# lab1_yakimenko_usb_i2c.net
KiCad netlist of a schematic drawn in Altium Designer
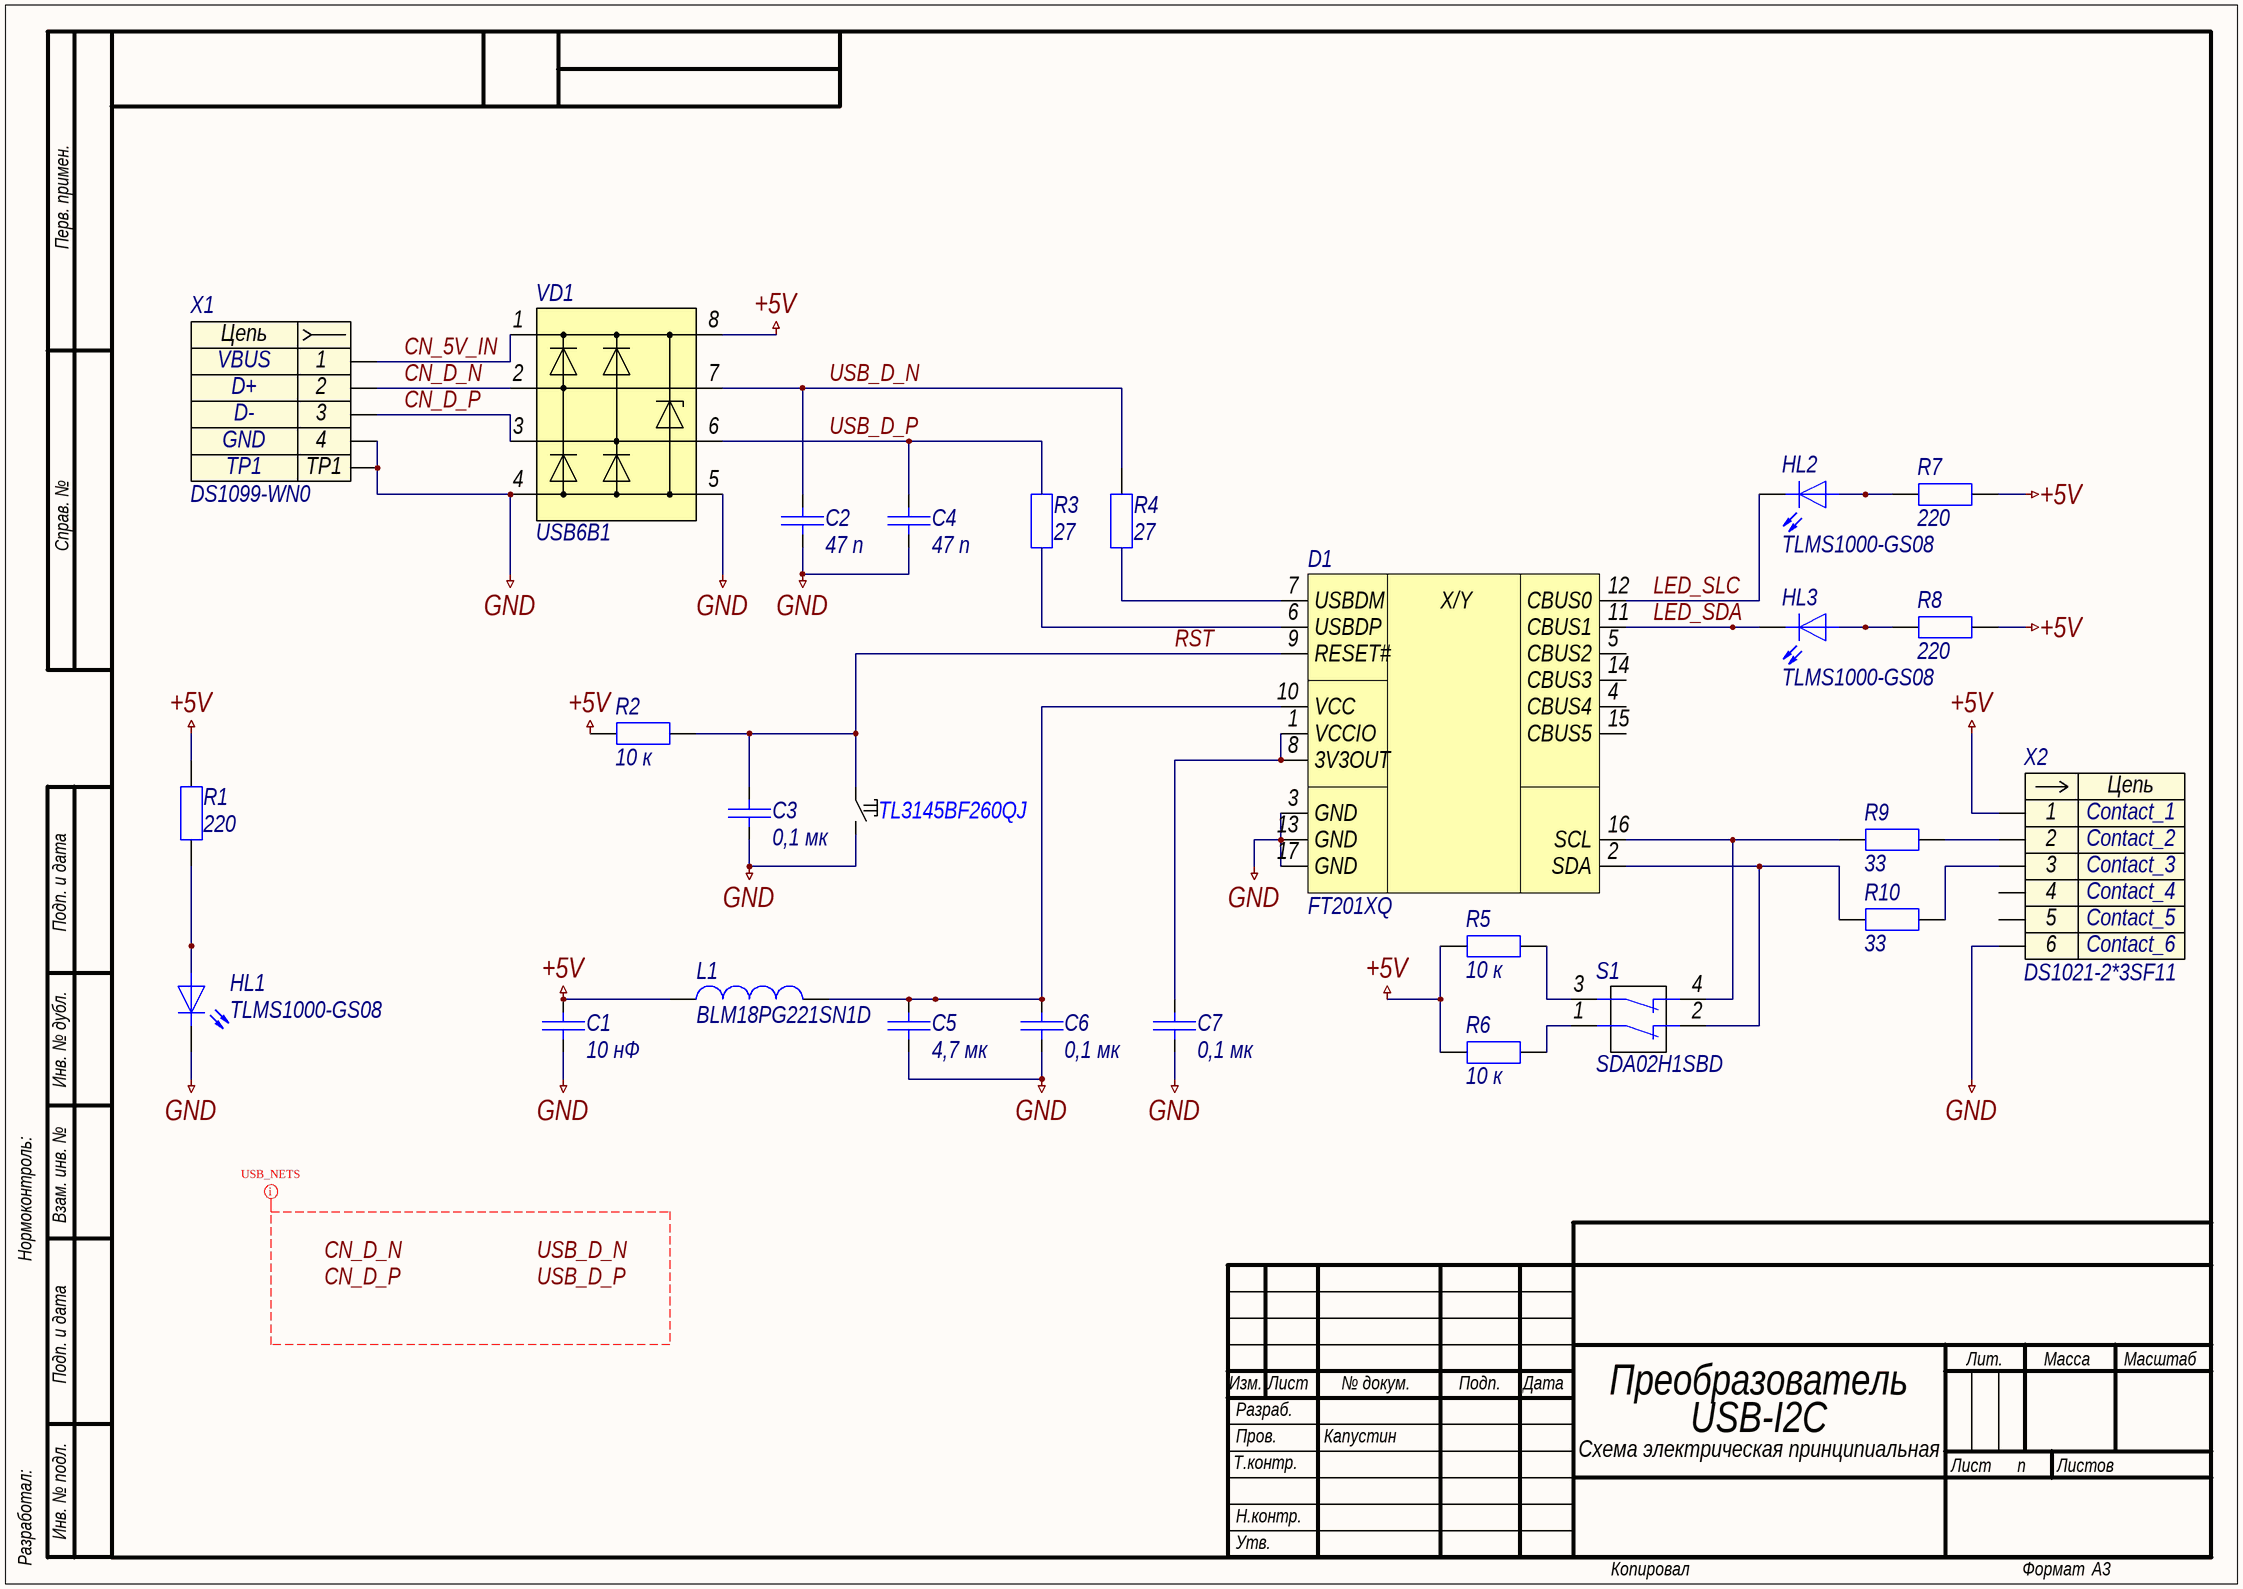
[diagram p0: lab1_yakimenko_usb_i2c.SchDoc]

(export (version "E")
  (design (tool "Eeschema 10.0.6"))
  (components
    (comp (ref "C1")
      (value "10 нФ")
      (footprint "C0402")
      (description "=Описание")
      (libsource (lib "Database_Students") (part "C-NONPOLAR"))
    )
    (comp (ref "C2")
      (value "47 п")
      (footprint "C0201")
      (description "=Описание")
      (libsource (lib "Database_Students") (part "C-NONPOLAR"))
    )
    (comp (ref "C3")
      (value "0,1 мк")
      (footprint "C0603")
      (description "=Описание")
      (libsource (lib "Database_Students") (part "C-NONPOLAR"))
    )
    (comp (ref "C4")
      (value "47 п")
      (footprint "C0201")
      (description "=Описание")
      (libsource (lib "Database_Students") (part "C-NONPOLAR"))
    )
    (comp (ref "C5")
      (value "4,7 мк")
      (footprint "C0603")
      (description "=Описание")
      (libsource (lib "Database_Students") (part "C-NONPOLAR"))
    )
    (comp (ref "C6")
      (value "0,1 мк")
      (footprint "C0603")
      (description "=Описание")
      (libsource (lib "Database_Students") (part "C-NONPOLAR"))
    )
    (comp (ref "C7")
      (value "0,1 мк")
      (footprint "C0603")
      (description "=Описание")
      (libsource (lib "Database_Students") (part "C-NONPOLAR"))
    )
    (comp (ref "D1") (value "FT201XQ") (footprint "FT201XQ") (libsource (lib "Schlib1") (part "FT201XQ")))
    (comp (ref "HL1")
      (value "TLMS1000-GS08")
      (footprint "HL0603")
      (description "=Описание")
      (libsource (lib "Database_Students") (part "HL-COMMON"))
    )
    (comp (ref "HL2")
      (value "TLMS1000-GS08")
      (footprint "HL0603")
      (description "=Описание")
      (libsource (lib "Database_Students") (part "HL-COMMON"))
    )
    (comp (ref "HL3")
      (value "TLMS1000-GS08")
      (footprint "HL0603")
      (description "=Описание")
      (libsource (lib "Database_Students") (part "HL-COMMON"))
    )
    (comp (ref "L1")
      (value "BLM18PG221SN1D")
      (footprint "BLM-2-0603")
      (description "=Описание")
      (libsource (lib "Database_Students") (part "FERRITE-BEAD"))
    )
    (comp (ref "R1")
      (value "220")
      (footprint "R0603")
      (description "=Описание")
      (libsource (lib "Database_Students") (part "R-COMMON"))
    )
    (comp (ref "R2")
      (value "10 к")
      (footprint "R0603")
      (description "=Описание")
      (libsource (lib "Database_Students") (part "R-COMMON"))
    )
    (comp (ref "R3") (value "27") (footprint "R27") (libsource (lib "Schlib2") (part "R27")))
    (comp (ref "R4") (value "27") (footprint "R27") (libsource (lib "Schlib2") (part "R27")))
    (comp (ref "R5")
      (value "10 к")
      (footprint "R0603")
      (description "=Описание")
      (libsource (lib "Database_Students") (part "R-COMMON"))
    )
    (comp (ref "R6")
      (value "10 к")
      (footprint "R0603")
      (description "=Описание")
      (libsource (lib "Database_Students") (part "R-COMMON"))
    )
    (comp (ref "R7")
      (value "220")
      (footprint "R0603")
      (description "=Описание")
      (libsource (lib "Database_Students") (part "R-COMMON"))
    )
    (comp (ref "R8")
      (value "220")
      (footprint "R0603")
      (description "=Описание")
      (libsource (lib "Database_Students") (part "R-COMMON"))
    )
    (comp (ref "R9")
      (value "33")
      (footprint "R0603")
      (description "=Описание")
      (libsource (lib "Database_Students") (part "R-COMMON"))
    )
    (comp (ref "R10")
      (value "33")
      (footprint "R0603")
      (description "=Описание")
      (libsource (lib "Database_Students") (part "R-COMMON"))
    )
    (comp (ref "S1")
      (value "SDA02H1SBD")
      (footprint "DIP-SWITCH-02-706X930X545")
      (description "=Описание")
      (libsource (lib "Database_Students") (part "SWITCH-02"))
    )
    (comp (ref "TL3145BF260QJ")
      (value "~")
      (footprint "BUT: 3x4x2 SMT")
      (description "SMT 3*4*2 2PIN")
      (fields
        (field (name "MANUFACTURER") "xin cheng electronic")
        (field (name "VALUEMANUFACTURERPARTNUMBER") ", 3*4*2mm")
      )
      (libsource (lib "electromechanics") (part "Button_3x4x2_SMT"))
    )
    (comp (ref "VD1")
      (value "USB6B1")
      (footprint "SO-8")
      (description "=Описание")
      (libsource (lib "Database_Students") (part "USB6B1"))
    )
    (comp (ref "X1")
      (value "DS1099-WN0")
      (footprint "DS1099-WN0")
      (description "=Описание")
      (libsource (lib "Database_Students") (part "HEADER-4-TP1-SCT"))
    )
    (comp (ref "X2")
      (value "DS1021-2*3SF11")
      (footprint "DS1021-2X3SF11")
      (description "=Описание")
      (libsource (lib "Database_Students") (part "HEADER-6-PLG"))
    )
  )
  (nets
    (net (code "1") (name "+5V") (class "Default")
      (node (ref "C1") (pin "1") (pinfunction "1_1") (pintype "passive"))
      (node (ref "L1") (pin "1") (pinfunction "1_1") (pintype "passive"))
      (node (ref "R1") (pin "2") (pinfunction "2_2") (pintype "passive"))
      (node (ref "R2") (pin "1") (pinfunction "1_1") (pintype "passive"))
      (node (ref "R5") (pin "1") (pinfunction "1_1") (pintype "passive"))
      (node (ref "R6") (pin "1") (pinfunction "1_1") (pintype "passive"))
      (node (ref "R7") (pin "2") (pinfunction "2_2") (pintype "passive"))
      (node (ref "R8") (pin "2") (pinfunction "2_2") (pintype "passive"))
      (node (ref "VD1") (pin "8") (pinfunction "8_8") (pintype "passive"))
      (node (ref "X2") (pin "1") (pinfunction "1_1") (pintype "passive"))
    )
    (net (code "2") (name "/CN_5V_IN") (class "Default")
      (node (ref "VD1") (pin "1") (pinfunction "1_1") (pintype "passive"))
      (node (ref "X1") (pin "1") (pinfunction "1_1") (pintype "passive"))
    )
    (net (code "3") (name "/CN_D_N") (class "Default")
      (node (ref "VD1") (pin "2") (pinfunction "2_2") (pintype "passive"))
      (node (ref "X1") (pin "2") (pinfunction "2_2") (pintype "passive"))
    )
    (net (code "4") (name "/CN_D_P") (class "Default")
      (node (ref "VD1") (pin "3") (pinfunction "3_3") (pintype "passive"))
      (node (ref "X1") (pin "3") (pinfunction "3_3") (pintype "passive"))
    )
    (net (code "5") (name "/LED_SDA") (class "Default")
      (node (ref "D1") (pin "11") (pinfunction "CBUS1_11") (pintype "passive"))
      (node (ref "HL3") (pin "1") (pinfunction "1_1") (pintype "passive"))
    )
    (net (code "6") (name "/LED_SLC") (class "Default")
      (node (ref "D1") (pin "12") (pinfunction "CBUS0_12") (pintype "passive"))
      (node (ref "HL2") (pin "1") (pinfunction "1_1") (pintype "passive"))
    )
    (net (code "7") (name "/RST") (class "Default")
      (node (ref "C3") (pin "1") (pinfunction "1_1") (pintype "passive"))
      (node (ref "D1") (pin "9") (pinfunction "RESET#_9") (pintype "passive"))
      (node (ref "R2") (pin "2") (pinfunction "2_2") (pintype "passive"))
      (node (ref "TL3145BF260QJ") (pin "1") (pinfunction "1_1") (pintype "passive"))
    )
    (net (code "8") (name "/USB_D_N") (class "Default")
      (node (ref "C2") (pin "1") (pinfunction "1_1") (pintype "passive"))
      (node (ref "VD1") (pin "7") (pinfunction "7_7") (pintype "passive"))
    )
    (net (code "9") (name "/USB_D_P") (class "Default")
      (node (ref "C4") (pin "1") (pinfunction "1_1") (pintype "passive"))
      (node (ref "R3") (pin "2") (pinfunction "2_2") (pintype "passive"))
      (node (ref "VD1") (pin "6") (pinfunction "6_6") (pintype "passive"))
    )
    (net (code "10") (name "GND") (class "Default")
      (node (ref "C1") (pin "2") (pinfunction "2_2") (pintype "passive"))
      (node (ref "C2") (pin "2") (pinfunction "2_2") (pintype "passive"))
      (node (ref "C3") (pin "2") (pinfunction "2_2") (pintype "passive"))
      (node (ref "C4") (pin "2") (pinfunction "2_2") (pintype "passive"))
      (node (ref "C5") (pin "2") (pinfunction "2_2") (pintype "passive"))
      (node (ref "C6") (pin "2") (pinfunction "2_2") (pintype "passive"))
      (node (ref "C7") (pin "2") (pinfunction "2_2") (pintype "passive"))
      (node (ref "D1") (pin "13") (pinfunction "GND_13") (pintype "passive"))
      (node (ref "D1") (pin "17") (pinfunction "GND_17") (pintype "passive"))
      (node (ref "D1") (pin "3") (pinfunction "GND_3") (pintype "passive"))
      (node (ref "HL1") (pin "1") (pinfunction "1_1") (pintype "passive"))
      (node (ref "TL3145BF260QJ") (pin "2") (pinfunction "2_2") (pintype "passive"))
      (node (ref "VD1") (pin "4") (pinfunction "4_4") (pintype "passive"))
      (node (ref "VD1") (pin "5") (pinfunction "5_5") (pintype "passive"))
      (node (ref "X1") (pin "4") (pinfunction "4_4") (pintype "passive"))
      (node (ref "X1") (pin "TP1") (pinfunction "TP1_TP1") (pintype "passive"))
      (node (ref "X2") (pin "6") (pinfunction "6_6") (pintype "passive"))
    )
    (net (code "11") (name "Net-(D1-3V3OUT)") (class "Default")
      (node (ref "C7") (pin "1") (pinfunction "1_1") (pintype "passive"))
      (node (ref "D1") (pin "1") (pinfunction "VCCIO_1") (pintype "passive"))
      (node (ref "D1") (pin "8") (pinfunction "3V3OUT_8") (pintype "passive"))
    )
    (net (code "12") (name "Net-(D1-SCL)") (class "Default")
      (node (ref "D1") (pin "16") (pinfunction "SCL_16") (pintype "passive"))
      (node (ref "R9") (pin "1") (pinfunction "1_1") (pintype "passive"))
      (node (ref "S1") (pin "4") (pinfunction "4_4") (pintype "passive"))
    )
    (net (code "13") (name "Net-(D1-SDA)") (class "Default")
      (node (ref "D1") (pin "2") (pinfunction "SDA_2") (pintype "passive"))
      (node (ref "R10") (pin "1") (pinfunction "1_1") (pintype "passive"))
      (node (ref "S1") (pin "2") (pinfunction "2_2") (pintype "passive"))
    )
    (net (code "14") (name "Net-(D1-USBDM)") (class "Default")
      (node (ref "D1") (pin "7") (pinfunction "USBDM_7") (pintype "passive"))
      (node (ref "R4") (pin "1") (pinfunction "1_1") (pintype "passive"))
    )
    (net (code "15") (name "Net-(D1-USBDP)") (class "Default")
      (node (ref "D1") (pin "6") (pinfunction "USBDP_6") (pintype "passive"))
      (node (ref "R3") (pin "1") (pinfunction "1_1") (pintype "passive"))
    )
    (net (code "16") (name "Net-(D1-VCC)") (class "Default")
      (node (ref "C5") (pin "1") (pinfunction "1_1") (pintype "passive"))
      (node (ref "C6") (pin "1") (pinfunction "1_1") (pintype "passive"))
      (node (ref "D1") (pin "10") (pinfunction "VCC_10") (pintype "passive"))
      (node (ref "L1") (pin "2") (pinfunction "2_2") (pintype "passive"))
    )
    (net (code "17") (name "Net-(HL1-Pad2)") (class "Default")
      (node (ref "HL1") (pin "2") (pinfunction "2_2") (pintype "passive"))
      (node (ref "R1") (pin "1") (pinfunction "1_1") (pintype "passive"))
    )
    (net (code "18") (name "Net-(HL2-Pad2)") (class "Default")
      (node (ref "HL2") (pin "2") (pinfunction "2_2") (pintype "passive"))
      (node (ref "R7") (pin "1") (pinfunction "1_1") (pintype "passive"))
    )
    (net (code "19") (name "Net-(HL3-Pad2)") (class "Default")
      (node (ref "HL3") (pin "2") (pinfunction "2_2") (pintype "passive"))
      (node (ref "R8") (pin "1") (pinfunction "1_1") (pintype "passive"))
    )
    (net (code "20") (name "Net-(R5-Pad2)") (class "Default")
      (node (ref "R5") (pin "2") (pinfunction "2_2") (pintype "passive"))
      (node (ref "S1") (pin "3") (pinfunction "3_3") (pintype "passive"))
    )
    (net (code "21") (name "Net-(R6-Pad2)") (class "Default")
      (node (ref "R6") (pin "2") (pinfunction "2_2") (pintype "passive"))
      (node (ref "S1") (pin "1") (pinfunction "1_1") (pintype "passive"))
    )
    (net (code "22") (name "Net-(R9-Pad2)") (class "Default")
      (node (ref "R9") (pin "2") (pinfunction "2_2") (pintype "passive"))
      (node (ref "X2") (pin "2") (pinfunction "2_2") (pintype "passive"))
    )
    (net (code "23") (name "Net-(R10-Pad2)") (class "Default")
      (node (ref "R10") (pin "2") (pinfunction "2_2") (pintype "passive"))
      (node (ref "X2") (pin "3") (pinfunction "3_3") (pintype "passive"))
    )
    (net (code "24") (name "unconnected-(D1-CBUS2-Pad5)") (class "Default")
      (node (ref "D1") (pin "5") (pinfunction "CBUS2_5") (pintype "passive"))
    )
    (net (code "25") (name "unconnected-(D1-CBUS3-Pad14)") (class "Default")
      (node (ref "D1") (pin "14") (pinfunction "CBUS3_14") (pintype "passive"))
    )
    (net (code "26") (name "unconnected-(D1-CBUS4-Pad4)") (class "Default")
      (node (ref "D1") (pin "4") (pinfunction "CBUS4_4") (pintype "passive"))
    )
    (net (code "27") (name "unconnected-(D1-CBUS5-Pad15)") (class "Default")
      (node (ref "D1") (pin "15") (pinfunction "CBUS5_15") (pintype "passive"))
    )
    (net (code "28") (name "unconnected-(R4-Pad2)") (class "Default")
      (node (ref "R4") (pin "2") (pinfunction "2_2") (pintype "passive"))
    )
    (net (code "29") (name "unconnected-(X2-Pad4)") (class "Default")
      (node (ref "X2") (pin "4") (pinfunction "4_4") (pintype "passive"))
    )
    (net (code "30") (name "unconnected-(X2-Pad5)") (class "Default")
      (node (ref "X2") (pin "5") (pinfunction "5_5") (pintype "passive"))
    )
  )
)
